# 54HC595_SHIFT_REGISTER_BOARD_1.net
KiCad netlist of a schematic drawn in EAGLE
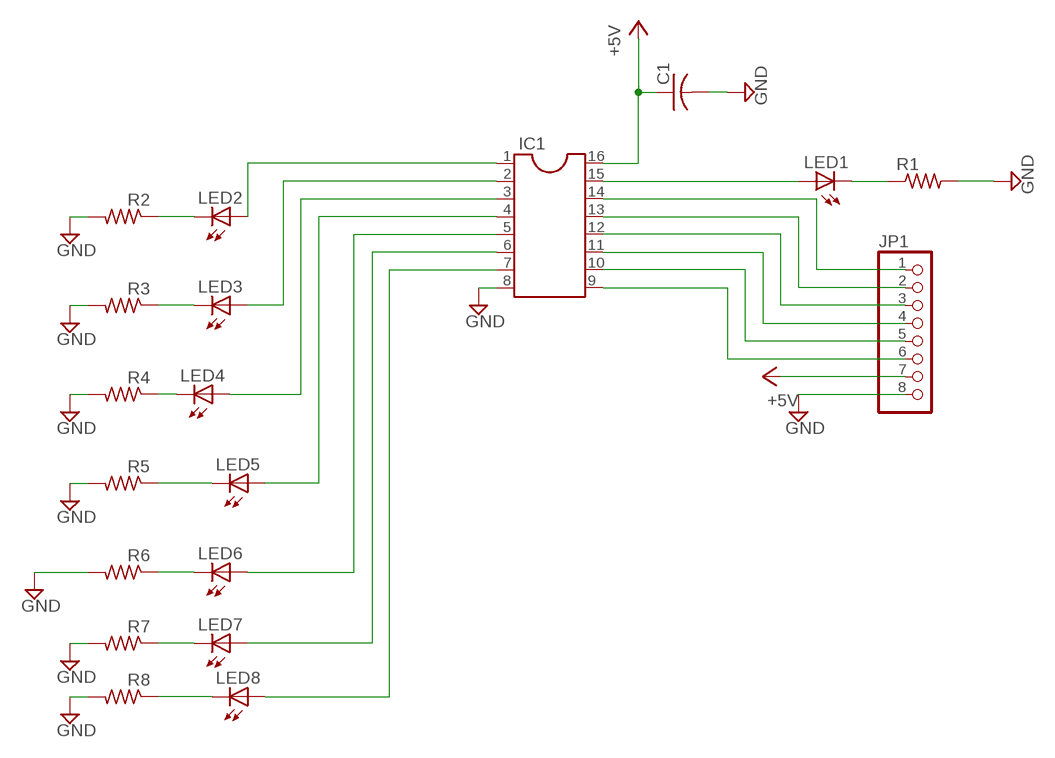
[diagram p0: schematic, sheet 1]

(export (version "E")
  (design (tool "Eeschema 10.0.6"))
  (components
    (comp (ref "C1")
      (value "C-US050-025X075")
      (footprint "eagle-import:C050-025X075")
      (libsource (lib "eagle-import") (part "C-US050-025X075"))
    )
    (comp (ref "IC1")
      (value "DIL16")
      (footprint "eagle-import:DIL16")
      (libsource (lib "eagle-import") (part "DIL16"))
    )
    (comp (ref "JP1")
      (value "PINHD-1X8")
      (footprint "eagle-import:1X08")
      (libsource (lib "eagle-import") (part "PINHD-1X8"))
    )
    (comp (ref "LED1")
      (value "LEDCHIPLED_0805")
      (footprint "eagle-import:CHIPLED_0805")
      (libsource (lib "eagle-import") (part "LEDCHIPLED_0805"))
    )
    (comp (ref "LED2")
      (value "LEDCHIPLED_0805")
      (footprint "eagle-import:CHIPLED_0805")
      (libsource (lib "eagle-import") (part "LEDCHIPLED_0805"))
    )
    (comp (ref "LED3")
      (value "LEDCHIPLED_0805")
      (footprint "eagle-import:CHIPLED_0805")
      (libsource (lib "eagle-import") (part "LEDCHIPLED_0805"))
    )
    (comp (ref "LED4")
      (value "LEDCHIPLED_0805")
      (footprint "eagle-import:CHIPLED_0805")
      (libsource (lib "eagle-import") (part "LEDCHIPLED_0805"))
    )
    (comp (ref "LED5")
      (value "LEDCHIPLED_0805")
      (footprint "eagle-import:CHIPLED_0805")
      (libsource (lib "eagle-import") (part "LEDCHIPLED_0805"))
    )
    (comp (ref "LED6")
      (value "LEDCHIPLED_0805")
      (footprint "eagle-import:CHIPLED_0805")
      (libsource (lib "eagle-import") (part "LEDCHIPLED_0805"))
    )
    (comp (ref "LED7")
      (value "LEDCHIPLED_0805")
      (footprint "eagle-import:CHIPLED_0805")
      (libsource (lib "eagle-import") (part "LEDCHIPLED_0805"))
    )
    (comp (ref "LED8")
      (value "LEDCHIPLED_0805")
      (footprint "eagle-import:CHIPLED_0805")
      (libsource (lib "eagle-import") (part "LEDCHIPLED_0805"))
    )
    (comp (ref "R1")
      (value "R-US_0309/V")
      (footprint "eagle-import:0309V")
      (libsource (lib "eagle-import") (part "R-US_0309/V"))
    )
    (comp (ref "R2")
      (value "R-US_0309/V")
      (footprint "eagle-import:0309V")
      (libsource (lib "eagle-import") (part "R-US_0309/V"))
    )
    (comp (ref "R3")
      (value "R-US_0309/V")
      (footprint "eagle-import:0309V")
      (libsource (lib "eagle-import") (part "R-US_0309/V"))
    )
    (comp (ref "R4")
      (value "R-US_0309/V")
      (footprint "eagle-import:0309V")
      (libsource (lib "eagle-import") (part "R-US_0309/V"))
    )
    (comp (ref "R5")
      (value "R-US_0309/V")
      (footprint "eagle-import:0309V")
      (libsource (lib "eagle-import") (part "R-US_0309/V"))
    )
    (comp (ref "R6")
      (value "R-US_0309/V")
      (footprint "eagle-import:0309V")
      (libsource (lib "eagle-import") (part "R-US_0309/V"))
    )
    (comp (ref "R7")
      (value "R-US_0309/V")
      (footprint "eagle-import:0309V")
      (libsource (lib "eagle-import") (part "R-US_0309/V"))
    )
    (comp (ref "R8")
      (value "R-US_0309/V")
      (footprint "eagle-import:0309V")
      (libsource (lib "eagle-import") (part "R-US_0309/V"))
    )
  )
  (nets
    (net (code "1") (name "+5V") (class "Default")
      (node (ref "C1") (pin "1") (pinfunction "1_1") (pintype "passive"))
      (node (ref "IC1") (pin "16") (pinfunction "16_16") (pintype "passive"))
      (node (ref "JP1") (pin "7") (pinfunction "7_7") (pintype "passive"))
    )
    (net (code "2") (name "GND") (class "Default")
      (node (ref "C1") (pin "2") (pinfunction "2_2") (pintype "passive"))
      (node (ref "IC1") (pin "8") (pinfunction "8_8") (pintype "passive"))
      (node (ref "JP1") (pin "8") (pinfunction "8_8") (pintype "passive"))
      (node (ref "R1") (pin "2") (pinfunction "2_2") (pintype "passive"))
      (node (ref "R2") (pin "2") (pinfunction "2_2") (pintype "passive"))
      (node (ref "R3") (pin "2") (pinfunction "2_2") (pintype "passive"))
      (node (ref "R4") (pin "2") (pinfunction "2_2") (pintype "passive"))
      (node (ref "R5") (pin "2") (pinfunction "2_2") (pintype "passive"))
      (node (ref "R6") (pin "2") (pinfunction "2_2") (pintype "passive"))
      (node (ref "R7") (pin "2") (pinfunction "2_2") (pintype "passive"))
      (node (ref "R8") (pin "2") (pinfunction "2_2") (pintype "passive"))
    )
    (net (code "3") (name "Net-(IC1-Pad1)") (class "Default")
      (node (ref "IC1") (pin "1") (pinfunction "1_1") (pintype "passive"))
      (node (ref "LED2") (pin "A") (pinfunction "A_A") (pintype "passive"))
    )
    (net (code "4") (name "Net-(IC1-Pad2)") (class "Default")
      (node (ref "IC1") (pin "2") (pinfunction "2_2") (pintype "passive"))
      (node (ref "LED3") (pin "A") (pinfunction "A_A") (pintype "passive"))
    )
    (net (code "5") (name "Net-(IC1-Pad3)") (class "Default")
      (node (ref "IC1") (pin "3") (pinfunction "3_3") (pintype "passive"))
      (node (ref "LED4") (pin "A") (pinfunction "A_A") (pintype "passive"))
    )
    (net (code "6") (name "Net-(IC1-Pad4)") (class "Default")
      (node (ref "IC1") (pin "4") (pinfunction "4_4") (pintype "passive"))
      (node (ref "LED5") (pin "A") (pinfunction "A_A") (pintype "passive"))
    )
    (net (code "7") (name "Net-(IC1-Pad5)") (class "Default")
      (node (ref "IC1") (pin "5") (pinfunction "5_5") (pintype "passive"))
      (node (ref "LED6") (pin "A") (pinfunction "A_A") (pintype "passive"))
    )
    (net (code "8") (name "Net-(IC1-Pad6)") (class "Default")
      (node (ref "IC1") (pin "6") (pinfunction "6_6") (pintype "passive"))
      (node (ref "LED7") (pin "A") (pinfunction "A_A") (pintype "passive"))
    )
    (net (code "9") (name "Net-(IC1-Pad7)") (class "Default")
      (node (ref "IC1") (pin "7") (pinfunction "7_7") (pintype "passive"))
      (node (ref "LED8") (pin "A") (pinfunction "A_A") (pintype "passive"))
    )
    (net (code "10") (name "Net-(IC1-Pad9)") (class "Default")
      (node (ref "IC1") (pin "9") (pinfunction "9_9") (pintype "passive"))
      (node (ref "JP1") (pin "6") (pinfunction "6_6") (pintype "passive"))
    )
    (net (code "11") (name "Net-(IC1-Pad10)") (class "Default")
      (node (ref "IC1") (pin "10") (pinfunction "10_10") (pintype "passive"))
      (node (ref "JP1") (pin "5") (pinfunction "5_5") (pintype "passive"))
    )
    (net (code "12") (name "Net-(IC1-Pad11)") (class "Default")
      (node (ref "IC1") (pin "11") (pinfunction "11_11") (pintype "passive"))
      (node (ref "JP1") (pin "4") (pinfunction "4_4") (pintype "passive"))
    )
    (net (code "13") (name "Net-(IC1-Pad12)") (class "Default")
      (node (ref "IC1") (pin "12") (pinfunction "12_12") (pintype "passive"))
      (node (ref "JP1") (pin "3") (pinfunction "3_3") (pintype "passive"))
    )
    (net (code "14") (name "Net-(IC1-Pad13)") (class "Default")
      (node (ref "IC1") (pin "13") (pinfunction "13_13") (pintype "passive"))
      (node (ref "JP1") (pin "2") (pinfunction "2_2") (pintype "passive"))
    )
    (net (code "15") (name "Net-(IC1-Pad14)") (class "Default")
      (node (ref "IC1") (pin "14") (pinfunction "14_14") (pintype "passive"))
      (node (ref "JP1") (pin "1") (pinfunction "1_1") (pintype "passive"))
    )
    (net (code "16") (name "Net-(IC1-Pad15)") (class "Default")
      (node (ref "IC1") (pin "15") (pinfunction "15_15") (pintype "passive"))
      (node (ref "LED1") (pin "A") (pinfunction "A_A") (pintype "passive"))
    )
    (net (code "17") (name "Net-(LED1-PadC)") (class "Default")
      (node (ref "LED1") (pin "C") (pinfunction "C_C") (pintype "passive"))
      (node (ref "R1") (pin "1") (pinfunction "1_1") (pintype "passive"))
    )
    (net (code "18") (name "Net-(LED2-PadC)") (class "Default")
      (node (ref "LED2") (pin "C") (pinfunction "C_C") (pintype "passive"))
      (node (ref "R2") (pin "1") (pinfunction "1_1") (pintype "passive"))
    )
    (net (code "19") (name "Net-(LED3-PadC)") (class "Default")
      (node (ref "LED3") (pin "C") (pinfunction "C_C") (pintype "passive"))
      (node (ref "R3") (pin "1") (pinfunction "1_1") (pintype "passive"))
    )
    (net (code "20") (name "Net-(LED4-PadC)") (class "Default")
      (node (ref "LED4") (pin "C") (pinfunction "C_C") (pintype "passive"))
      (node (ref "R4") (pin "1") (pinfunction "1_1") (pintype "passive"))
    )
    (net (code "21") (name "Net-(LED5-PadC)") (class "Default")
      (node (ref "LED5") (pin "C") (pinfunction "C_C") (pintype "passive"))
      (node (ref "R5") (pin "1") (pinfunction "1_1") (pintype "passive"))
    )
    (net (code "22") (name "Net-(LED6-PadC)") (class "Default")
      (node (ref "LED6") (pin "C") (pinfunction "C_C") (pintype "passive"))
      (node (ref "R6") (pin "1") (pinfunction "1_1") (pintype "passive"))
    )
    (net (code "23") (name "Net-(LED7-PadC)") (class "Default")
      (node (ref "LED7") (pin "C") (pinfunction "C_C") (pintype "passive"))
      (node (ref "R7") (pin "1") (pinfunction "1_1") (pintype "passive"))
    )
    (net (code "24") (name "Net-(LED8-PadC)") (class "Default")
      (node (ref "LED8") (pin "C") (pinfunction "C_C") (pintype "passive"))
      (node (ref "R8") (pin "1") (pinfunction "1_1") (pintype "passive"))
    )
  )
)
